# IOT_ESP32-OUTLET.net
KiCad netlist of a schematic drawn in Altium Designer
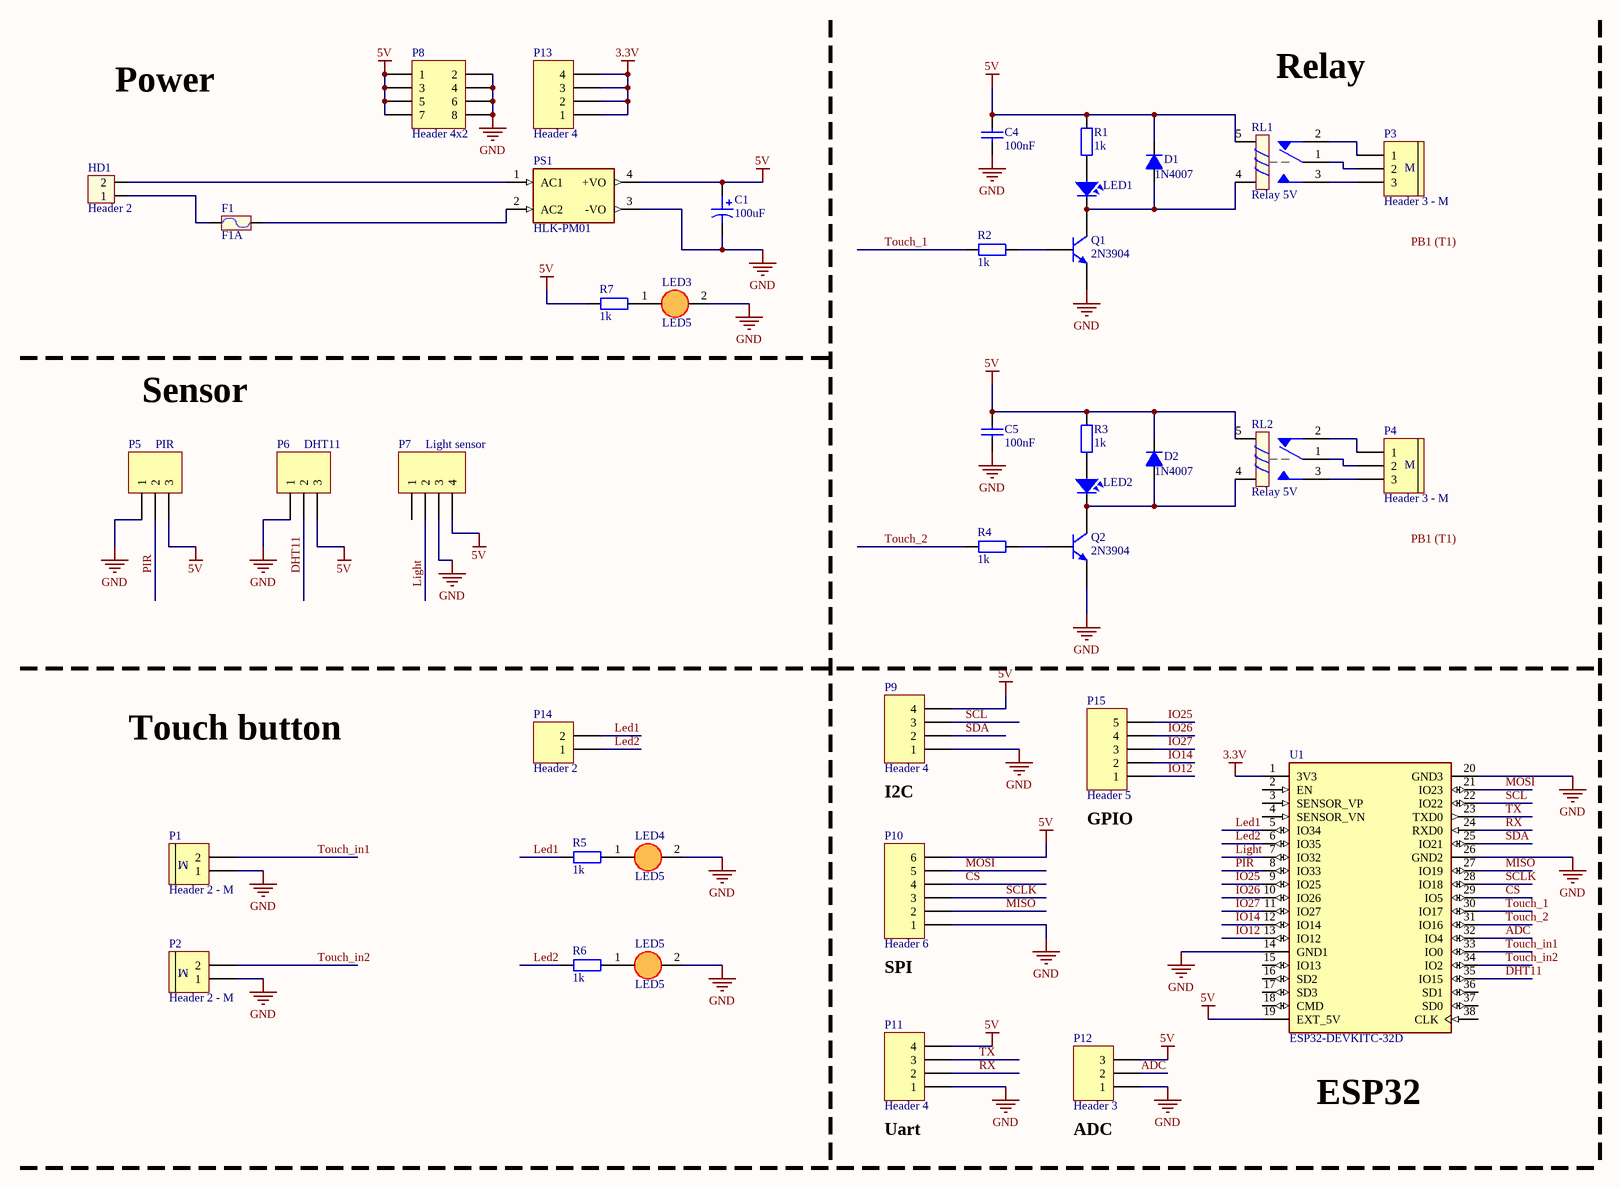
[diagram p0: IOT_ESP32-OUTLET.SchDoc]

(export (version "E")
  (design (tool "Eeschema 10.0.6"))
  (components
    (comp (ref "C1")
      (value "100uF")
      (footprint "RADIAL C")
      (description "Polarized Capacitor")
      (fields (field (name "Comment") "Cap Pol") (field (name "PUBLISHER") "Altium Limited"))
      (libsource (lib "hphonglib") (part "Cap Pol"))
    )
    (comp (ref "C4")
      (value "100nF")
      (footprint "Cap Non-Pol 3mm")
      (description "Non-polarized Capacitor")
      (fields (field (name "Comment") "Cap Non-pol") (field (name "PUBLISHER") "Altium Limited"))
      (libsource (lib "hphonglib") (part "Cap Non-pol"))
    )
    (comp (ref "C5")
      (value "100nF")
      (footprint "Cap Non-Pol 3mm")
      (description "Non-polarized Capacitor")
      (fields (field (name "Comment") "Cap Non-pol") (field (name "PUBLISHER") "Altium Limited"))
      (libsource (lib "hphonglib") (part "Cap Non-pol"))
    )
    (comp (ref "D1")
      (value "1N4007")
      (footprint "D1A")
      (description "Diode 1A")
      (libsource (lib "My Library") (part "D1A"))
    )
    (comp (ref "D2")
      (value "1N4007")
      (footprint "D1A")
      (description "Diode 1A")
      (libsource (lib "My Library") (part "D1A"))
    )
    (comp (ref "F1")
      (value "F1A")
      (footprint "Fuse")
      (description "Fuse")
      (fields (field (name "DESIGNED BY") "VanDungEvn"))
      (libsource (lib "syhaunguyen") (part "Fuse"))
    )
    (comp (ref "HD1")
      (value "Header 2")
      (footprint "HED2")
      (description "Header 2 (Green)")
      (libsource (lib "My Library") (part "Hed2"))
    )
    (comp (ref "LED1")
      (value "LED")
      (footprint "LED-3")
      (description "LED Single colour Green and Red")
      (libsource (lib "My Library") (part "LED"))
    )
    (comp (ref "LED2")
      (value "LED")
      (footprint "LED-3")
      (description "LED Single colour Green and Red")
      (libsource (lib "My Library") (part "LED"))
    )
    (comp (ref "LED3")
      (value "LED5")
      (footprint "LED5MM")
      (description "LED 5mm")
      (libsource (lib "My Library") (part "LED 5mm"))
    )
    (comp (ref "LED4")
      (value "LED5")
      (footprint "LED5MM")
      (description "LED 5mm")
      (libsource (lib "My Library") (part "LED 5mm"))
    )
    (comp (ref "LED5")
      (value "LED5")
      (footprint "LED5MM")
      (description "LED 5mm")
      (libsource (lib "My Library") (part "LED 5mm"))
    )
    (comp (ref "P1")
      (value "Header 2 - M")
      (footprint "Medium - Header 2")
      (description "Header, 2-Pin, Medium")
      (fields (field (name "PUBLISHER") "Altium Limited"))
      (libsource (lib "hphonglib") (part "Header 2 - M"))
    )
    (comp (ref "P2")
      (value "Header 2 - M")
      (footprint "Medium - Header 2")
      (description "Header, 2-Pin, Medium")
      (fields (field (name "PUBLISHER") "Altium Limited"))
      (libsource (lib "hphonglib") (part "Header 2 - M"))
    )
    (comp (ref "P3")
      (value "Header 3 - M")
      (footprint "Medium - Header 3")
      (description "Header, 3-Pin, Medium")
      (fields (field (name "PUBLISHER") "Altium Limited"))
      (libsource (lib "My Library") (part "Header 3 - M"))
    )
    (comp (ref "P4")
      (value "Header 3 - M")
      (footprint "Medium - Header 3")
      (description "Header, 3-Pin, Medium")
      (fields (field (name "PUBLISHER") "Altium Limited"))
      (libsource (lib "My Library") (part "Header 3 - M"))
    )
    (comp (ref "P5")
      (value "PIR")
      (footprint "Header 3")
      (description "Header, 3-Pin")
      (fields (field (name "PUBLISHER") "Altium Limited"))
      (libsource (lib "") (part "Header 3_1"))
    )
    (comp (ref "P6")
      (value "DHT11")
      (footprint "Header 3")
      (description "Header, 3-Pin")
      (fields (field (name "PUBLISHER") "Altium Limited"))
      (libsource (lib "") (part "Header 3_1"))
    )
    (comp (ref "P7")
      (value "Light sensor")
      (footprint "HDR1X4")
      (description "Header, 4-Pin")
      (fields (field (name "PUBLISHER") "Altium Limited"))
      (libsource (lib "My Library") (part "Header 4"))
    )
    (comp (ref "P8")
      (value "Header 4x2")
      (footprint "Header 4x2")
      (description "Header, 8-Pin, 2-Row")
      (fields (field (name "PUBLISHER") "Altium Limited"))
      (libsource (lib "hphonglib") (part "Header 4x2"))
    )
    (comp (ref "P9")
      (value "Header 4")
      (footprint "Header 4")
      (description "Header, 4-Pin")
      (fields (field (name "PUBLISHER") "Altium Limited"))
      (libsource (lib "hphonglib") (part "Header 4"))
    )
    (comp (ref "P10")
      (value "Header 6")
      (footprint "Header 6")
      (description "Header, 6-Pin")
      (fields (field (name "PUBLISHER") "Altium Limited"))
      (libsource (lib "hphonglib") (part "Header 6"))
    )
    (comp (ref "P11")
      (value "Header 4")
      (footprint "Header 4")
      (description "Header, 4-Pin")
      (fields (field (name "PUBLISHER") "Altium Limited"))
      (libsource (lib "hphonglib") (part "Header 4"))
    )
    (comp (ref "P12")
      (value "Header 3")
      (footprint "Header 3")
      (description "Header, 3-Pin")
      (fields (field (name "PUBLISHER") "Altium Limited"))
      (libsource (lib "hphonglib") (part "Header 3"))
    )
    (comp (ref "P13")
      (value "Header 4")
      (footprint "HDR1X4")
      (description "Header, 4-Pin")
      (fields (field (name "PUBLISHER") "Altium Limited"))
      (libsource (lib "") (part "Header 4_1"))
    )
    (comp (ref "P14")
      (value "Header 2")
      (footprint "HDR1X2")
      (description "Header, 2-Pin")
      (fields (field (name "PUBLISHER") "Altium Limited"))
      (libsource (lib "My Library") (part "Header 2"))
    )
    (comp (ref "P15")
      (value "Header 5")
      (footprint "HDR1X5")
      (description "Header, 5-Pin")
      (fields (field (name "PUBLISHER") "Altium Limited"))
      (libsource (lib "My Library") (part "Header 5"))
    )
    (comp (ref "PS1")
      (value "HLK-PM01")
      (footprint "CONV_HLK-PM01")
      (fields (field (name "MF") "Hi-link") (field (name "MP") "hlk-pm01"))
      (libsource (lib "HLK-PM01") (part "HLK-PM01"))
    )
    (comp (ref "Q1")
      (value "2N3904")
      (footprint "TO-92A")
      (description "NPN General Purpose Amplifier")
      (fields (field (name "PUBLISHER") "Altium Limited"))
      (libsource (lib "Miscellaneous Devices") (part "2N3904"))
    )
    (comp (ref "Q2")
      (value "2N3904")
      (footprint "TO-92A")
      (description "NPN General Purpose Amplifier")
      (fields (field (name "PUBLISHER") "Altium Limited"))
      (libsource (lib "Miscellaneous Devices") (part "2N3904"))
    )
    (comp (ref "R1")
      (value "1k")
      (footprint "R1/4W")
      (description "Resistor 1/4W")
      (libsource (lib "My Library") (part "R1/4W"))
    )
    (comp (ref "R2")
      (value "1k")
      (footprint "R1/4W")
      (description "Resistor 1/4W")
      (libsource (lib "My Library") (part "R1/4W"))
    )
    (comp (ref "R3")
      (value "1k")
      (footprint "R1/4W")
      (description "Resistor 1/4W")
      (libsource (lib "My Library") (part "R1/4W"))
    )
    (comp (ref "R4")
      (value "1k")
      (footprint "R1/4W")
      (description "Resistor 1/4W")
      (libsource (lib "My Library") (part "R1/4W"))
    )
    (comp (ref "R5")
      (value "1k")
      (footprint "R1/4W")
      (description "Resistor 1/4W")
      (libsource (lib "My Library") (part "R1/4W"))
    )
    (comp (ref "R6")
      (value "1k")
      (footprint "R1/4W")
      (description "Resistor 1/4W")
      (libsource (lib "My Library") (part "R1/4W"))
    )
    (comp (ref "R7")
      (value "1k")
      (footprint "R1/4W")
      (description "Resistor 1/4W")
      (libsource (lib "My Library") (part "R1/4W"))
    )
    (comp (ref "RL1")
      (value "Relay 5V")
      (footprint "RL_SPDT_10A")
      (description "Relay SPDT,10A - 12VDC 5 Pin")
      (libsource (lib "hphonglib") (part "Relay 1"))
    )
    (comp (ref "RL2")
      (value "Relay 5V")
      (footprint "RL_SPDT_10A")
      (description "Relay SPDT,10A - 12VDC 5 Pin")
      (libsource (lib "hphonglib") (part "Relay 1"))
    )
    (comp (ref "U1")
      (value "ESP32-DEVKITC-32D")
      (footprint "MODULE_ESP32-DEVKITC-32D")
      (description "Eval Board For Esp-Wroom-32")
      (libsource (lib "ESP32-DEVKITC-32D") (part "ESP32-DEVKITC-32D"))
    )
  )
  (nets
    (net (code "1") (name "/ADC") (class "Default")
      (node (ref "P12") (pin "2") (pinfunction "2_2") (pintype "passive"))
      (node (ref "U1") (pin "32") (pinfunction "IO4_32") (pintype "bidirectional"))
    )
    (net (code "2") (name "/CS") (class "Default")
      (node (ref "P10") (pin "4") (pinfunction "4_4") (pintype "passive"))
      (node (ref "U1") (pin "29") (pinfunction "IO5_29") (pintype "bidirectional"))
    )
    (net (code "3") (name "/DHT11") (class "Default")
      (node (ref "P6") (pin "2") (pinfunction "2_2") (pintype "passive"))
      (node (ref "U1") (pin "35") (pinfunction "IO15_35") (pintype "bidirectional"))
    )
    (net (code "4") (name "/IO12") (class "Default")
      (node (ref "P15") (pin "1") (pinfunction "1_1") (pintype "passive"))
      (node (ref "U1") (pin "13") (pinfunction "IO12_13") (pintype "bidirectional"))
    )
    (net (code "5") (name "/IO14") (class "Default")
      (node (ref "P15") (pin "2") (pinfunction "2_2") (pintype "passive"))
      (node (ref "U1") (pin "12") (pinfunction "IO14_12") (pintype "bidirectional"))
    )
    (net (code "6") (name "/IO25") (class "Default")
      (node (ref "P15") (pin "5") (pinfunction "5_5") (pintype "passive"))
      (node (ref "U1") (pin "9") (pinfunction "IO25_9") (pintype "bidirectional"))
    )
    (net (code "7") (name "/IO26") (class "Default")
      (node (ref "P15") (pin "4") (pinfunction "4_4") (pintype "passive"))
      (node (ref "U1") (pin "10") (pinfunction "IO26_10") (pintype "bidirectional"))
    )
    (net (code "8") (name "/IO27") (class "Default")
      (node (ref "P15") (pin "3") (pinfunction "3_3") (pintype "passive"))
      (node (ref "U1") (pin "11") (pinfunction "IO27_11") (pintype "bidirectional"))
    )
    (net (code "9") (name "/Led1") (class "Default")
      (node (ref "P14") (pin "2") (pinfunction "2_2") (pintype "passive"))
      (node (ref "R5") (pin "1") (pinfunction "1_1") (pintype "passive"))
      (node (ref "U1") (pin "5") (pinfunction "IO34_5") (pintype "bidirectional"))
    )
    (net (code "10") (name "/Led2") (class "Default")
      (node (ref "P14") (pin "1") (pinfunction "1_1") (pintype "passive"))
      (node (ref "R6") (pin "1") (pinfunction "1_1") (pintype "passive"))
      (node (ref "U1") (pin "6") (pinfunction "IO35_6") (pintype "bidirectional"))
    )
    (net (code "11") (name "/Light") (class "Default")
      (node (ref "P7") (pin "2") (pinfunction "2_2") (pintype "passive"))
      (node (ref "U1") (pin "7") (pinfunction "IO32_7") (pintype "bidirectional"))
    )
    (net (code "12") (name "/MISO") (class "Default")
      (node (ref "P10") (pin "2") (pinfunction "2_2") (pintype "passive"))
      (node (ref "U1") (pin "27") (pinfunction "IO19_27") (pintype "bidirectional"))
    )
    (net (code "13") (name "/MOSI") (class "Default")
      (node (ref "P10") (pin "5") (pinfunction "5_5") (pintype "passive"))
      (node (ref "U1") (pin "21") (pinfunction "IO23_21") (pintype "bidirectional"))
    )
    (net (code "15") (name "/PIR") (class "Default")
      (node (ref "P5") (pin "2") (pinfunction "2_2") (pintype "passive"))
      (node (ref "U1") (pin "8") (pinfunction "IO33_8") (pintype "bidirectional"))
    )
    (net (code "16") (name "/RX") (class "Default")
      (node (ref "P11") (pin "2") (pinfunction "2_2") (pintype "passive"))
      (node (ref "U1") (pin "24") (pinfunction "RXD0_24") (pintype "input"))
    )
    (net (code "17") (name "/SCL") (class "Default")
      (node (ref "P9") (pin "3") (pinfunction "3_3") (pintype "passive"))
      (node (ref "U1") (pin "22") (pinfunction "IO22_22") (pintype "bidirectional"))
    )
    (net (code "18") (name "/SCLK") (class "Default")
      (node (ref "P10") (pin "3") (pinfunction "3_3") (pintype "passive"))
      (node (ref "U1") (pin "28") (pinfunction "IO18_28") (pintype "bidirectional"))
    )
    (net (code "19") (name "/SDA") (class "Default")
      (node (ref "P9") (pin "2") (pinfunction "2_2") (pintype "passive"))
      (node (ref "U1") (pin "25") (pinfunction "IO21_25") (pintype "bidirectional"))
    )
    (net (code "20") (name "/TX") (class "Default")
      (node (ref "P11") (pin "3") (pinfunction "3_3") (pintype "passive"))
      (node (ref "U1") (pin "23") (pinfunction "TXD0_23") (pintype "output"))
    )
    (net (code "21") (name "/Touch_1") (class "Default")
      (node (ref "R2") (pin "2") (pinfunction "2_2") (pintype "passive"))
      (node (ref "U1") (pin "30") (pinfunction "IO17_30") (pintype "bidirectional"))
    )
    (net (code "22") (name "/Touch_2") (class "Default")
      (node (ref "R4") (pin "2") (pinfunction "2_2") (pintype "passive"))
      (node (ref "U1") (pin "31") (pinfunction "IO16_31") (pintype "bidirectional"))
    )
    (net (code "23") (name "/Touch_in1") (class "Default")
      (node (ref "P1") (pin "2") (pinfunction "2_2") (pintype "passive"))
      (node (ref "U1") (pin "33") (pinfunction "IO0_33") (pintype "bidirectional"))
    )
    (net (code "24") (name "/Touch_in2") (class "Default")
      (node (ref "P2") (pin "2") (pinfunction "2_2") (pintype "passive"))
      (node (ref "U1") (pin "34") (pinfunction "IO2_34") (pintype "bidirectional"))
    )
    (net (code "25") (name "3.3V") (class "Default")
      (node (ref "P13") (pin "1") (pinfunction "1_1") (pintype "passive"))
      (node (ref "P13") (pin "2") (pinfunction "2_2") (pintype "passive"))
      (node (ref "P13") (pin "3") (pinfunction "3_3") (pintype "passive"))
      (node (ref "P13") (pin "4") (pinfunction "4_4") (pintype "passive"))
      (node (ref "U1") (pin "1") (pinfunction "3V3_1") (pintype "power_in"))
    )
    (net (code "26") (name "5V") (class "Default")
      (node (ref "C1") (pin "1") (pinfunction "1_1") (pintype "passive"))
      (node (ref "C4") (pin "2") (pinfunction "2_2") (pintype "passive"))
      (node (ref "C5") (pin "2") (pinfunction "2_2") (pintype "passive"))
      (node (ref "D1") (pin "2") (pinfunction "K_2") (pintype "passive"))
      (node (ref "D2") (pin "2") (pinfunction "K_2") (pintype "passive"))
      (node (ref "P10") (pin "6") (pinfunction "6_6") (pintype "passive"))
      (node (ref "P11") (pin "4") (pinfunction "4_4") (pintype "passive"))
      (node (ref "P12") (pin "3") (pinfunction "3_3") (pintype "passive"))
      (node (ref "P5") (pin "3") (pinfunction "3_3") (pintype "passive"))
      (node (ref "P6") (pin "3") (pinfunction "3_3") (pintype "passive"))
      (node (ref "P7") (pin "4") (pinfunction "4_4") (pintype "passive"))
      (node (ref "P8") (pin "1") (pinfunction "1_1") (pintype "passive"))
      (node (ref "P8") (pin "3") (pinfunction "3_3") (pintype "passive"))
      (node (ref "P8") (pin "5") (pinfunction "5_5") (pintype "passive"))
      (node (ref "P8") (pin "7") (pinfunction "7_7") (pintype "passive"))
      (node (ref "P9") (pin "4") (pinfunction "4_4") (pintype "passive"))
      (node (ref "PS1") (pin "4") (pinfunction "+VO_4") (pintype "output"))
      (node (ref "R1") (pin "2") (pinfunction "2_2") (pintype "passive"))
      (node (ref "R3") (pin "2") (pinfunction "2_2") (pintype "passive"))
      (node (ref "R7") (pin "1") (pinfunction "1_1") (pintype "passive"))
      (node (ref "RL1") (pin "5") (pinfunction "5_5") (pintype "passive"))
      (node (ref "RL2") (pin "5") (pinfunction "5_5") (pintype "passive"))
      (node (ref "U1") (pin "19") (pinfunction "EXT_5V_19") (pintype "power_in"))
    )
    (net (code "27") (name "GND") (class "Default")
      (node (ref "C1") (pin "2") (pinfunction "2_2") (pintype "passive"))
      (node (ref "C4") (pin "1") (pinfunction "1_1") (pintype "passive"))
      (node (ref "C5") (pin "1") (pinfunction "1_1") (pintype "passive"))
      (node (ref "LED3") (pin "2") (pinfunction "K_2") (pintype "passive"))
      (node (ref "LED4") (pin "2") (pinfunction "K_2") (pintype "passive"))
      (node (ref "LED5") (pin "2") (pinfunction "K_2") (pintype "passive"))
      (node (ref "P1") (pin "1") (pinfunction "1_1") (pintype "passive"))
      (node (ref "P10") (pin "1") (pinfunction "1_1") (pintype "passive"))
      (node (ref "P11") (pin "1") (pinfunction "1_1") (pintype "passive"))
      (node (ref "P12") (pin "1") (pinfunction "1_1") (pintype "passive"))
      (node (ref "P2") (pin "1") (pinfunction "1_1") (pintype "passive"))
      (node (ref "P5") (pin "1") (pinfunction "1_1") (pintype "passive"))
      (node (ref "P6") (pin "1") (pinfunction "1_1") (pintype "passive"))
      (node (ref "P7") (pin "3") (pinfunction "3_3") (pintype "passive"))
      (node (ref "P8") (pin "2") (pinfunction "2_2") (pintype "passive"))
      (node (ref "P8") (pin "4") (pinfunction "4_4") (pintype "passive"))
      (node (ref "P8") (pin "6") (pinfunction "6_6") (pintype "passive"))
      (node (ref "P8") (pin "8") (pinfunction "8_8") (pintype "passive"))
      (node (ref "P9") (pin "1") (pinfunction "1_1") (pintype "passive"))
      (node (ref "PS1") (pin "3") (pinfunction "-VO_3") (pintype "output"))
      (node (ref "Q1") (pin "1") (pinfunction "E_1") (pintype "passive"))
      (node (ref "Q2") (pin "1") (pinfunction "E_1") (pintype "passive"))
      (node (ref "U1") (pin "14") (pinfunction "GND1_14") (pintype "power_in"))
      (node (ref "U1") (pin "20") (pinfunction "GND3_20") (pintype "power_in"))
      (node (ref "U1") (pin "26") (pinfunction "GND2_26") (pintype "power_in"))
    )
    (net (code "28") (name "Net-(D1-A)") (class "Default")
      (node (ref "D1") (pin "1") (pinfunction "A_1") (pintype "passive"))
      (node (ref "LED1") (pin "2") (pinfunction "2_2") (pintype "passive"))
      (node (ref "Q1") (pin "3") (pinfunction "C_3") (pintype "passive"))
      (node (ref "RL1") (pin "4") (pinfunction "4_4") (pintype "passive"))
    )
    (net (code "29") (name "Net-(D2-A)") (class "Default")
      (node (ref "D2") (pin "1") (pinfunction "A_1") (pintype "passive"))
      (node (ref "LED2") (pin "2") (pinfunction "2_2") (pintype "passive"))
      (node (ref "Q2") (pin "3") (pinfunction "C_3") (pintype "passive"))
      (node (ref "RL2") (pin "4") (pinfunction "4_4") (pintype "passive"))
    )
    (net (code "30") (name "Net-(F1-Pad1)") (class "Default")
      (node (ref "F1") (pin "1") (pinfunction "1_1") (pintype "passive"))
      (node (ref "HD1") (pin "1") (pinfunction "1_1") (pintype "passive"))
    )
    (net (code "31") (name "Net-(LED1-Pad1)") (class "Default")
      (node (ref "LED1") (pin "1") (pinfunction "1_1") (pintype "passive"))
      (node (ref "R1") (pin "1") (pinfunction "1_1") (pintype "passive"))
    )
    (net (code "32") (name "Net-(LED2-Pad1)") (class "Default")
      (node (ref "LED2") (pin "1") (pinfunction "1_1") (pintype "passive"))
      (node (ref "R3") (pin "1") (pinfunction "1_1") (pintype "passive"))
    )
    (net (code "33") (name "Net-(LED3-A)") (class "Default")
      (node (ref "LED3") (pin "1") (pinfunction "A_1") (pintype "passive"))
      (node (ref "R7") (pin "2") (pinfunction "2_2") (pintype "passive"))
    )
    (net (code "34") (name "Net-(LED4-A)") (class "Default")
      (node (ref "LED4") (pin "1") (pinfunction "A_1") (pintype "passive"))
      (node (ref "R5") (pin "2") (pinfunction "2_2") (pintype "passive"))
    )
    (net (code "35") (name "Net-(LED5-A)") (class "Default")
      (node (ref "LED5") (pin "1") (pinfunction "A_1") (pintype "passive"))
      (node (ref "R6") (pin "2") (pinfunction "2_2") (pintype "passive"))
    )
    (net (code "36") (name "Net-(P3-Pad1)") (class "Default")
      (node (ref "P3") (pin "1") (pinfunction "1_1") (pintype "passive"))
      (node (ref "RL1") (pin "2") (pinfunction "2_2") (pintype "passive"))
    )
    (net (code "37") (name "Net-(P3-Pad2)") (class "Default")
      (node (ref "P3") (pin "2") (pinfunction "2_2") (pintype "passive"))
      (node (ref "RL1") (pin "1") (pinfunction "1_1") (pintype "passive"))
    )
    (net (code "38") (name "Net-(P3-Pad3)") (class "Default")
      (node (ref "P3") (pin "3") (pinfunction "3_3") (pintype "passive"))
      (node (ref "RL1") (pin "3") (pinfunction "3_3") (pintype "passive"))
    )
    (net (code "39") (name "Net-(P4-Pad1)") (class "Default")
      (node (ref "P4") (pin "1") (pinfunction "1_1") (pintype "passive"))
      (node (ref "RL2") (pin "2") (pinfunction "2_2") (pintype "passive"))
    )
    (net (code "40") (name "Net-(P4-Pad2)") (class "Default")
      (node (ref "P4") (pin "2") (pinfunction "2_2") (pintype "passive"))
      (node (ref "RL2") (pin "1") (pinfunction "1_1") (pintype "passive"))
    )
    (net (code "41") (name "Net-(P4-Pad3)") (class "Default")
      (node (ref "P4") (pin "3") (pinfunction "3_3") (pintype "passive"))
      (node (ref "RL2") (pin "3") (pinfunction "3_3") (pintype "passive"))
    )
    (net (code "42") (name "Net-(PS1-AC1)") (class "Default")
      (node (ref "HD1") (pin "2") (pinfunction "2_2") (pintype "passive"))
      (node (ref "PS1") (pin "1") (pinfunction "AC1_1") (pintype "input"))
    )
    (net (code "43") (name "Net-(PS1-AC2)") (class "Default")
      (node (ref "F1") (pin "2") (pinfunction "2_2") (pintype "passive"))
      (node (ref "PS1") (pin "2") (pinfunction "AC2_2") (pintype "input"))
    )
    (net (code "44") (name "Net-(Q1-B)") (class "Default")
      (node (ref "Q1") (pin "2") (pinfunction "B_2") (pintype "passive"))
      (node (ref "R2") (pin "1") (pinfunction "1_1") (pintype "passive"))
    )
    (net (code "45") (name "Net-(Q2-B)") (class "Default")
      (node (ref "Q2") (pin "2") (pinfunction "B_2") (pintype "passive"))
      (node (ref "R4") (pin "1") (pinfunction "1_1") (pintype "passive"))
    )
    (net (code "46") (name "unconnected-(P7-Pad1)") (class "Default")
      (node (ref "P7") (pin "1") (pinfunction "1_1") (pintype "passive"))
    )
    (net (code "47") (name "unconnected-(U1-CLK-Pad38)") (class "Default")
      (node (ref "U1") (pin "38") (pinfunction "CLK_38") (pintype "input"))
    )
    (net (code "48") (name "unconnected-(U1-CMD-Pad18)") (class "Default")
      (node (ref "U1") (pin "18") (pinfunction "CMD_18") (pintype "bidirectional"))
    )
    (net (code "49") (name "unconnected-(U1-EN-Pad2)") (class "Default")
      (node (ref "U1") (pin "2") (pinfunction "EN_2") (pintype "input"))
    )
    (net (code "50") (name "unconnected-(U1-IO13-Pad15)") (class "Default")
      (node (ref "U1") (pin "15") (pinfunction "IO13_15") (pintype "bidirectional"))
    )
    (net (code "51") (name "unconnected-(U1-SD0-Pad37)") (class "Default")
      (node (ref "U1") (pin "37") (pinfunction "SD0_37") (pintype "bidirectional"))
    )
    (net (code "52") (name "unconnected-(U1-SD1-Pad36)") (class "Default")
      (node (ref "U1") (pin "36") (pinfunction "SD1_36") (pintype "bidirectional"))
    )
    (net (code "53") (name "unconnected-(U1-SD2-Pad16)") (class "Default")
      (node (ref "U1") (pin "16") (pinfunction "SD2_16") (pintype "bidirectional"))
    )
    (net (code "54") (name "unconnected-(U1-SD3-Pad17)") (class "Default")
      (node (ref "U1") (pin "17") (pinfunction "SD3_17") (pintype "bidirectional"))
    )
    (net (code "55") (name "unconnected-(U1-SENSOR_VN-Pad4)") (class "Default")
      (node (ref "U1") (pin "4") (pinfunction "SENSOR_VN_4") (pintype "input"))
    )
    (net (code "56") (name "unconnected-(U1-SENSOR_VP-Pad3)") (class "Default")
      (node (ref "U1") (pin "3") (pinfunction "SENSOR_VP_3") (pintype "input"))
    )
  )
)
